# VCO_core.net
KiCad netlist of a schematic drawn in Altium Designer
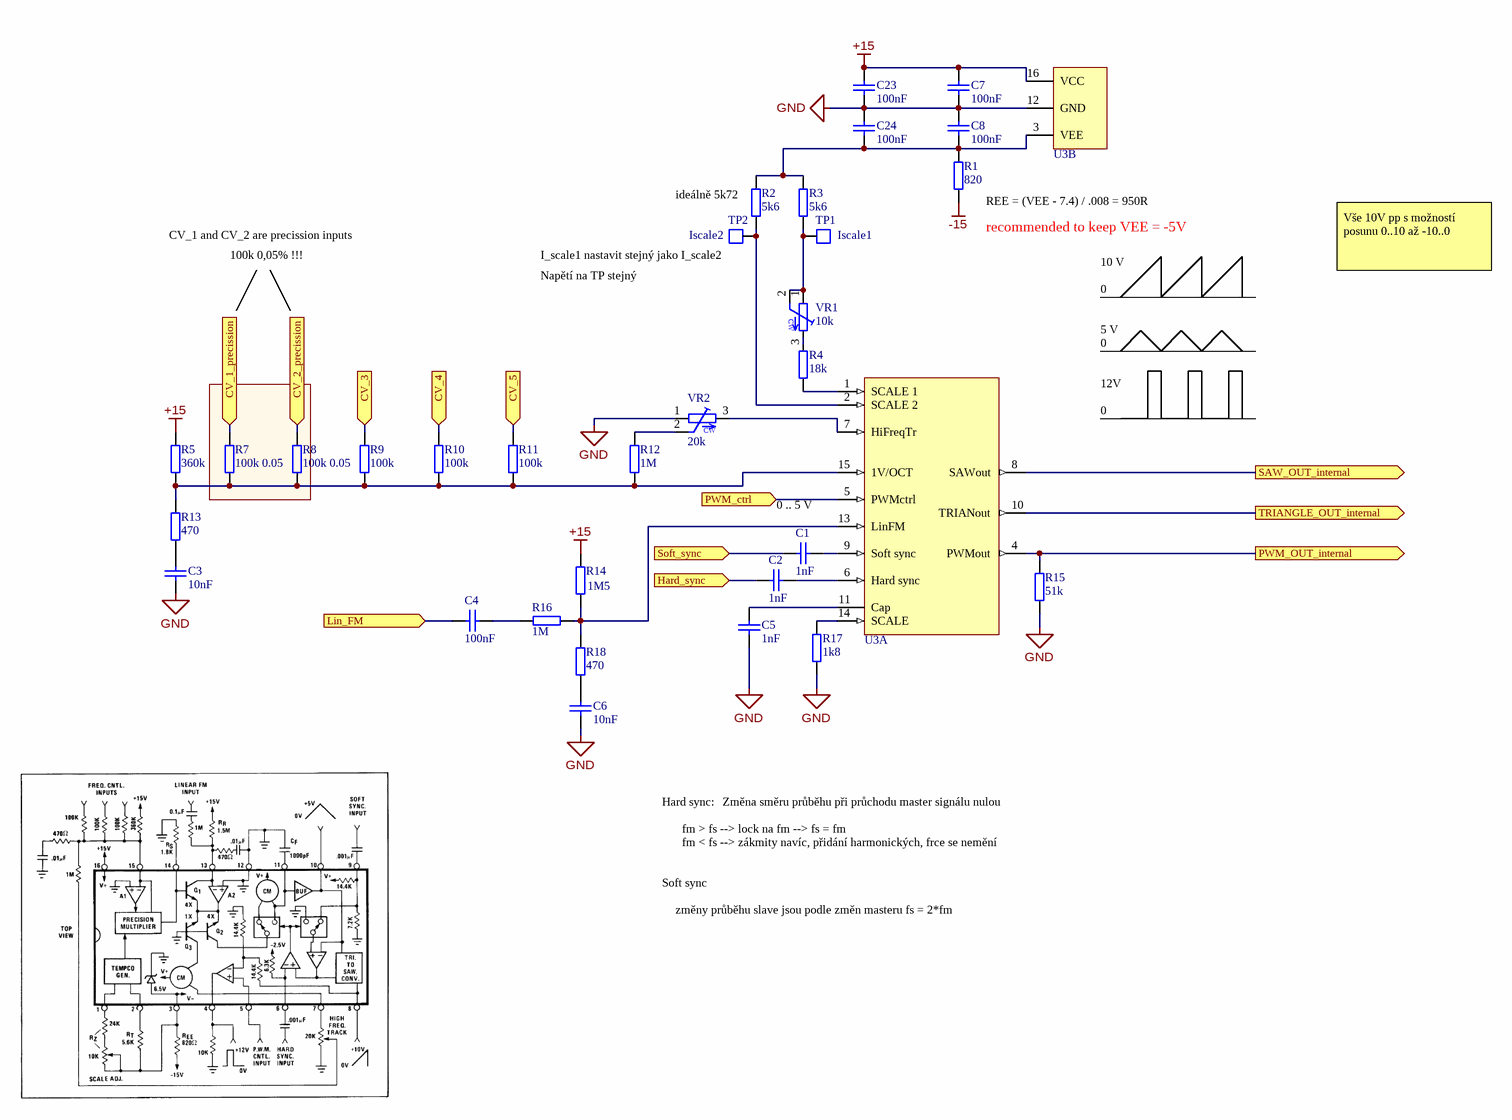
[diagram p0: VCO_core.SchDoc]

(export (version "E")
  (design (tool "Eeschema 10.0.6"))
  (components
    (comp (ref "C1")
      (value "1nF")
      (footprint "WCAP-CSGP_0603_L1.6W0.8H0.8_Reflow")
      (description "WCAP-CSGP Multilayer Ceramic Chip Capacitor, General Purpose, size 0603, NP0, 1nF, 50V")
      (fields
        (field (name "MANUFACTURER") "Wurth Elektronik")
        (field (name "MANUFACTURER PART NUMBER") "885012006063")
      )
      (libsource (lib "Altium_WCAP-CSGP (rev22a)") (part "885012006063"))
    )
    (comp (ref "C2")
      (value "1nF")
      (footprint "WCAP-CSGP_0603_L1.6W0.8H0.8_Reflow")
      (description "WCAP-CSGP Multilayer Ceramic Chip Capacitor, General Purpose, size 0603, NP0, 1nF, 50V")
      (fields
        (field (name "MANUFACTURER") "Wurth Elektronik")
        (field (name "MANUFACTURER PART NUMBER") "885012006063")
      )
      (libsource (lib "Altium_WCAP-CSGP (rev22a)") (part "885012006063"))
    )
    (comp (ref "C3")
      (value "10nF")
      (footprint "WCAP-CSGP_0603_L1.6W0.8H0.8_Reflow")
      (description "WCAP-CSGP Multilayer Ceramic Chip Capacitor, General Purpose, size 0603, X7R, 10nF, 50V")
      (fields
        (field (name "MANUFACTURER") "Wurth Elektronik")
        (field (name "MANUFACTURER PART NUMBER") "885012206089")
      )
      (libsource (lib "Altium_WCAP-CSGP (rev22a)") (part "885012206089"))
    )
    (comp (ref "C4")
      (value "100nF")
      (footprint "WCAP-CSGP_0603_L1.6W0.8H0.8_Reflow")
      (description "WCAP-CSGP Multilayer Ceramic Chip Capacitor, General Purpose, size 0603, X7R, 100nF, 50V")
      (fields
        (field (name "MANUFACTURER") "Wurth Elektronik")
        (field (name "MANUFACTURER PART NUMBER") "885012206095")
      )
      (libsource (lib "Altium_WCAP-CSGP (rev22a)") (part "885012206095"))
    )
    (comp (ref "C5")
      (value "1nF")
      (footprint "WCAP-CSGP_0603_L1.6W0.8H0.8_Reflow")
      (description "WCAP-CSGP Multilayer Ceramic Chip Capacitor, General Purpose, size 0603, NP0, 1nF, 50V")
      (fields
        (field (name "MANUFACTURER") "Wurth Elektronik")
        (field (name "MANUFACTURER PART NUMBER") "885012006063")
      )
      (libsource (lib "Altium_WCAP-CSGP (rev22a)") (part "885012006063"))
    )
    (comp (ref "C6")
      (value "10nF")
      (footprint "WCAP-CSGP_0603_L1.6W0.8H0.8_Reflow")
      (description "WCAP-CSGP Multilayer Ceramic Chip Capacitor, General Purpose, size 0603, X7R, 10nF, 50V")
      (fields
        (field (name "MANUFACTURER") "Wurth Elektronik")
        (field (name "MANUFACTURER PART NUMBER") "885012206089")
      )
      (libsource (lib "Altium_WCAP-CSGP (rev22a)") (part "885012206089"))
    )
    (comp (ref "C7")
      (value "100nF")
      (footprint "WCAP-CSGP_0603_L1.6W0.8H0.8_Reflow")
      (description "WCAP-CSGP Multilayer Ceramic Chip Capacitor, General Purpose, size 0603, X7R, 100nF, 50V")
      (fields
        (field (name "MANUFACTURER") "Wurth Elektronik")
        (field (name "MANUFACTURER PART NUMBER") "885012206095")
      )
      (libsource (lib "Altium_WCAP-CSGP (rev22a)") (part "885012206095"))
    )
    (comp (ref "C8")
      (value "100nF")
      (footprint "WCAP-CSGP_0603_L1.6W0.8H0.8_Reflow")
      (description "WCAP-CSGP Multilayer Ceramic Chip Capacitor, General Purpose, size 0603, X7R, 100nF, 50V")
      (fields
        (field (name "MANUFACTURER") "Wurth Elektronik")
        (field (name "MANUFACTURER PART NUMBER") "885012206095")
      )
      (libsource (lib "Altium_WCAP-CSGP (rev22a)") (part "885012206095"))
    )
    (comp (ref "C23")
      (value "100nF")
      (footprint "WCAP-CSGP_0603_L1.6W0.8H0.8_Reflow")
      (description "WCAP-CSGP Multilayer Ceramic Chip Capacitor, General Purpose, size 0603, X7R, 100nF, 50V")
      (fields
        (field (name "MANUFACTURER") "Wurth Elektronik")
        (field (name "MANUFACTURER PART NUMBER") "885012206095")
      )
      (libsource (lib "Altium_WCAP-CSGP (rev22a)") (part "885012206095"))
    )
    (comp (ref "C24")
      (value "100nF")
      (footprint "WCAP-CSGP_0603_L1.6W0.8H0.8_Reflow")
      (description "WCAP-CSGP Multilayer Ceramic Chip Capacitor, General Purpose, size 0603, X7R, 100nF, 50V")
      (fields
        (field (name "MANUFACTURER") "Wurth Elektronik")
        (field (name "MANUFACTURER PART NUMBER") "885012206095")
      )
      (libsource (lib "Altium_WCAP-CSGP (rev22a)") (part "885012206095"))
    )
    (comp (ref "R1")
      (value "820")
      (footprint "RESC1608X06N(SMR0603)")
      (description "Thick Film resistor, 0603 Size, universal value, 0.1 W")
      (libsource (lib "Kubikova integrovana knihovna ") (part "R 0603 universal"))
    )
    (comp (ref "R2")
      (value "5k6")
      (footprint "RESC1608X06N(SMR0603)")
      (description "Thick Film resistor, 0603 Size, universal value, 0.1 W")
      (libsource (lib "Kubikova integrovana knihovna ") (part "R 0603 universal"))
    )
    (comp (ref "R3")
      (value "5k6")
      (footprint "RESC1608X06N(SMR0603)")
      (description "Thick Film resistor, 0603 Size, universal value, 0.1 W")
      (libsource (lib "Kubikova integrovana knihovna ") (part "R 0603 universal"))
    )
    (comp (ref "R4")
      (value "18k")
      (footprint "RESC1608X06N(SMR0603)")
      (description "Thick Film resistor, 0603 Size, universal value, 0.1 W")
      (libsource (lib "Kubikova integrovana knihovna ") (part "R 0603 universal"))
    )
    (comp (ref "R5")
      (value "360k")
      (footprint "RESC1608X06N(SMR0603)")
      (description "Thick Film resistor, 0603 Size, universal value, 0.1 W")
      (libsource (lib "Kubikova integrovana knihovna ") (part "R 0603 universal"))
    )
    (comp (ref "R7")
      (value "100k 0.05")
      (footprint "RESC1608X06N(SMR0603)")
      (description "Precision Thick Film resistor, 0603 Size, universal value, 0.1 W")
      (libsource (lib "Kubikova integrovana knihovna ") (part "R 0603 universal"))
    )
    (comp (ref "R8")
      (value "100k 0.05")
      (footprint "RESC1608X06N(SMR0603)")
      (description "Precision Thick Film resistor, 0603 Size, universal value, 0.1 W")
      (libsource (lib "Kubikova integrovana knihovna ") (part "R 0603 universal"))
    )
    (comp (ref "R9")
      (value "100k")
      (footprint "RESC1608X06N(SMR0603)")
      (description "Thick Film resistor, 0603 Size, universal value, 0.1 W")
      (libsource (lib "Kubikova integrovana knihovna ") (part "R 0603 universal"))
    )
    (comp (ref "R10")
      (value "100k")
      (footprint "RESC1608X06N(SMR0603)")
      (description "Thick Film resistor, 0603 Size, universal value, 0.1 W")
      (libsource (lib "Kubikova integrovana knihovna ") (part "R 0603 universal"))
    )
    (comp (ref "R11")
      (value "100k")
      (footprint "RESC1608X06N(SMR0603)")
      (description "Thick Film resistor, 0603 Size, universal value, 0.1 W")
      (libsource (lib "Kubikova integrovana knihovna ") (part "R 0603 universal"))
    )
    (comp (ref "R12")
      (value "1M")
      (footprint "RESC1608X06N(SMR0603)")
      (description "Thick Film resistor, 0603 Size, universal value, 0.1 W")
      (libsource (lib "Kubikova integrovana knihovna ") (part "R 0603 universal"))
    )
    (comp (ref "R13")
      (value "470")
      (footprint "RESC1608X06N(SMR0603)")
      (description "Thick Film resistor, 0603 Size, universal value, 0.1 W")
      (libsource (lib "Kubikova integrovana knihovna ") (part "R 0603 universal"))
    )
    (comp (ref "R14")
      (value "1M5")
      (footprint "RESC1608X06N(SMR0603)")
      (description "Thick Film resistor, 0603 Size, universal value, 0.1 W")
      (libsource (lib "Kubikova integrovana knihovna ") (part "R 0603 universal"))
    )
    (comp (ref "R15")
      (value "51k")
      (footprint "RESC1608X06N(SMR0603)")
      (description "Thick Film resistor, 0603 Size, universal value, 0.1 W")
      (libsource (lib "Kubikova integrovana knihovna ") (part "R 0603 universal"))
    )
    (comp (ref "R16")
      (value "1M")
      (footprint "RESC1608X06N(SMR0603)")
      (description "Thick Film resistor, 0603 Size, universal value, 0.1 W")
      (libsource (lib "Kubikova integrovana knihovna ") (part "R 0603 universal"))
    )
    (comp (ref "R17")
      (value "1k8")
      (footprint "RESC1608X06N(SMR0603)")
      (description "Thick Film resistor, 0603 Size, universal value, 0.1 W")
      (libsource (lib "Kubikova integrovana knihovna ") (part "R 0603 universal"))
    )
    (comp (ref "R18")
      (value "470")
      (footprint "RESC1608X06N(SMR0603)")
      (description "Thick Film resistor, 0603 Size, universal value, 0.1 W")
      (libsource (lib "Kubikova integrovana knihovna ") (part "R 0603 universal"))
    )
    (comp (ref "TP1")
      (value "Iscale1")
      (footprint "TP_1.5_SMD_ROUND")
      (description "De; Test Point;")
      (libsource (lib "altium_sql") (part "TEST_POINT_SMD_ROUND"))
    )
    (comp (ref "TP2")
      (value "Iscale2")
      (footprint "TP_1.5_SMD_ROUND")
      (description "De; Test Point;")
      (libsource (lib "altium_sql") (part "TEST_POINT_SMD_ROUND"))
    )
    (comp (ref "U3")
      (value "CEM3340")
      (footprint "DIP-16")
      (description "ALFA RPAR AS3340 VCO (CEM3340)")
      (libsource (lib "") (part "CEM3340_1"))
    )
    (comp (ref "VR1")
      (value "10k")
      (footprint "64W")
      (description "093 - 3/8\" Square (10 mm) Multi-Turn Cermet Trimmer")
      (libsource (lib "Kubikova integrovana knihovna ") (part "Trimmer universal 3/8 (10mm)"))
    )
    (comp (ref "VR2")
      (value "20k")
      (footprint "64W")
      (description "093 - 3/8\" Square (10 mm) Multi-Turn Cermet Trimmer")
      (libsource (lib "Kubikova integrovana knihovna ") (part "Trimmer universal 3/8 (10mm)"))
    )
  )
  (nets
    (net (code "1") (name "+15") (class "Default")
      (node (ref "C23") (pin "2") (pinfunction "2_2") (pintype "passive"))
      (node (ref "C7") (pin "2") (pinfunction "2_2") (pintype "passive"))
      (node (ref "R14") (pin "2") (pinfunction "2_2") (pintype "passive"))
      (node (ref "R5") (pin "1") (pinfunction "1_1") (pintype "passive"))
      (node (ref "U3") (pin "16") (pinfunction "VCC_16") (pintype "power_in"))
    )
    (net (code "2") (name "-15") (class "Default")
      (node (ref "R1") (pin "1") (pinfunction "1_1") (pintype "passive"))
    )
    (net (code "3") (name "/CV_1_precission") (class "Default")
      (node (ref "R7") (pin "1") (pinfunction "1_1") (pintype "passive"))
    )
    (net (code "4") (name "/CV_2_precission") (class "Default")
      (node (ref "R8") (pin "1") (pinfunction "1_1") (pintype "passive"))
    )
    (net (code "5") (name "/CV_3") (class "Default")
      (node (ref "R9") (pin "1") (pinfunction "1_1") (pintype "passive"))
    )
    (net (code "6") (name "/CV_4") (class "Default")
      (node (ref "R10") (pin "1") (pinfunction "1_1") (pintype "passive"))
    )
    (net (code "7") (name "/CV_5") (class "Default")
      (node (ref "R11") (pin "1") (pinfunction "1_1") (pintype "passive"))
    )
    (net (code "8") (name "/Hard_sync") (class "Default")
      (node (ref "C2") (pin "1") (pinfunction "1_1") (pintype "passive"))
    )
    (net (code "9") (name "/Lin_FM") (class "Default")
      (node (ref "C4") (pin "1") (pinfunction "1_1") (pintype "passive"))
    )
    (net (code "10") (name "/PWM_OUT_internal") (class "Default")
      (node (ref "R15") (pin "2") (pinfunction "2_2") (pintype "passive"))
      (node (ref "U3") (pin "4") (pinfunction "PWMout_4") (pintype "output"))
    )
    (net (code "11") (name "/PWM_ctrl") (class "Default")
      (node (ref "U3") (pin "5") (pinfunction "PWMctrl_5") (pintype "input"))
    )
    (net (code "12") (name "/SAW_OUT_internal") (class "Default")
      (node (ref "U3") (pin "8") (pinfunction "SAWout_8") (pintype "output"))
    )
    (net (code "13") (name "/Soft_sync") (class "Default")
      (node (ref "C1") (pin "1") (pinfunction "1_1") (pintype "passive"))
    )
    (net (code "14") (name "/TRIANGLE_OUT_internal") (class "Default")
      (node (ref "U3") (pin "10") (pinfunction "TRIANout_10") (pintype "output"))
    )
    (net (code "15") (name "GND") (class "Default")
      (node (ref "C23") (pin "1") (pinfunction "1_1") (pintype "passive"))
      (node (ref "C24") (pin "2") (pinfunction "2_2") (pintype "passive"))
      (node (ref "C3") (pin "2") (pinfunction "2_2") (pintype "passive"))
      (node (ref "C5") (pin "1") (pinfunction "1_1") (pintype "passive"))
      (node (ref "C6") (pin "1") (pinfunction "1_1") (pintype "passive"))
      (node (ref "C7") (pin "1") (pinfunction "1_1") (pintype "passive"))
      (node (ref "C8") (pin "2") (pinfunction "2_2") (pintype "passive"))
      (node (ref "R15") (pin "1") (pinfunction "1_1") (pintype "passive"))
      (node (ref "R17") (pin "1") (pinfunction "1_1") (pintype "passive"))
      (node (ref "U3") (pin "12") (pinfunction "GND_12") (pintype "power_in"))
      (node (ref "VR2") (pin "1") (pinfunction "1_1") (pintype "passive"))
    )
    (net (code "16") (name "Net-(C3-Pad1)") (class "Default")
      (node (ref "C3") (pin "1") (pinfunction "1_1") (pintype "passive"))
      (node (ref "R13") (pin "2") (pinfunction "2_2") (pintype "passive"))
    )
    (net (code "17") (name "Net-(C4-Pad2)") (class "Default")
      (node (ref "C4") (pin "2") (pinfunction "2_2") (pintype "passive"))
      (node (ref "R16") (pin "2") (pinfunction "2_2") (pintype "passive"))
    )
    (net (code "18") (name "Net-(C6-Pad2)") (class "Default")
      (node (ref "C6") (pin "2") (pinfunction "2_2") (pintype "passive"))
      (node (ref "R18") (pin "1") (pinfunction "1_1") (pintype "passive"))
    )
    (net (code "19") (name "Net-(R3-Pad1)") (class "Default")
      (node (ref "R3") (pin "1") (pinfunction "1_1") (pintype "passive"))
      (node (ref "TP1") (pin "1") (pintype "passive"))
      (node (ref "VR1") (pin "1") (pinfunction "1_1") (pintype "passive"))
      (node (ref "VR1") (pin "2") (pinfunction "2_2") (pintype "passive"))
    )
    (net (code "20") (name "Net-(R4-Pad1)") (class "Default")
      (node (ref "R4") (pin "1") (pinfunction "1_1") (pintype "passive"))
      (node (ref "VR1") (pin "3") (pinfunction "3_3") (pintype "passive"))
    )
    (net (code "21") (name "Net-(R12-Pad2)") (class "Default")
      (node (ref "R12") (pin "2") (pinfunction "2_2") (pintype "passive"))
      (node (ref "VR2") (pin "2") (pinfunction "2_2") (pintype "passive"))
    )
    (net (code "22") (name "Net-(U3A-1V{slash}OCT)") (class "Default")
      (node (ref "R10") (pin "2") (pinfunction "2_2") (pintype "passive"))
      (node (ref "R11") (pin "2") (pinfunction "2_2") (pintype "passive"))
      (node (ref "R12") (pin "1") (pinfunction "1_1") (pintype "passive"))
      (node (ref "R13") (pin "1") (pinfunction "1_1") (pintype "passive"))
      (node (ref "R5") (pin "2") (pinfunction "2_2") (pintype "passive"))
      (node (ref "R7") (pin "2") (pinfunction "2_2") (pintype "passive"))
      (node (ref "R8") (pin "2") (pinfunction "2_2") (pintype "passive"))
      (node (ref "R9") (pin "2") (pinfunction "2_2") (pintype "passive"))
      (node (ref "U3") (pin "15") (pinfunction "1V/OCT_15") (pintype "input"))
    )
    (net (code "23") (name "Net-(U3A-Cap)") (class "Default")
      (node (ref "C5") (pin "2") (pinfunction "2_2") (pintype "passive"))
      (node (ref "U3") (pin "11") (pinfunction "Cap_11") (pintype "power_in"))
    )
    (net (code "24") (name "Net-(U3A-Hard_sync)") (class "Default")
      (node (ref "C2") (pin "2") (pinfunction "2_2") (pintype "passive"))
      (node (ref "U3") (pin "6") (pinfunction "Hard_sync_6") (pintype "input"))
    )
    (net (code "25") (name "Net-(U3A-HiFreqTr)") (class "Default")
      (node (ref "U3") (pin "7") (pinfunction "HiFreqTr_7") (pintype "input"))
      (node (ref "VR2") (pin "3") (pinfunction "3_3") (pintype "passive"))
    )
    (net (code "26") (name "Net-(U3A-LinFM)") (class "Default")
      (node (ref "R14") (pin "1") (pinfunction "1_1") (pintype "passive"))
      (node (ref "R16") (pin "1") (pinfunction "1_1") (pintype "passive"))
      (node (ref "R18") (pin "2") (pinfunction "2_2") (pintype "passive"))
      (node (ref "U3") (pin "13") (pinfunction "LinFM_13") (pintype "input"))
    )
    (net (code "27") (name "Net-(U3A-SCALE)") (class "Default")
      (node (ref "R17") (pin "2") (pinfunction "2_2") (pintype "passive"))
      (node (ref "U3") (pin "14") (pinfunction "SCALE_14") (pintype "input"))
    )
    (net (code "28") (name "Net-(U3A-SCALE_1)") (class "Default")
      (node (ref "R4") (pin "2") (pinfunction "2_2") (pintype "passive"))
      (node (ref "U3") (pin "1") (pinfunction "SCALE_1_1") (pintype "input"))
    )
    (net (code "29") (name "Net-(U3A-SCALE_2)") (class "Default")
      (node (ref "R2") (pin "1") (pinfunction "1_1") (pintype "passive"))
      (node (ref "TP2") (pin "1") (pintype "passive"))
      (node (ref "U3") (pin "2") (pinfunction "SCALE_2_2") (pintype "input"))
    )
    (net (code "30") (name "Net-(U3A-Soft_sync)") (class "Default")
      (node (ref "C1") (pin "2") (pinfunction "2_2") (pintype "passive"))
      (node (ref "U3") (pin "9") (pinfunction "Soft_sync_9") (pintype "input"))
    )
    (net (code "31") (name "Net-(U3B-VEE)") (class "Default")
      (node (ref "C24") (pin "1") (pinfunction "1_1") (pintype "passive"))
      (node (ref "C8") (pin "1") (pinfunction "1_1") (pintype "passive"))
      (node (ref "R1") (pin "2") (pinfunction "2_2") (pintype "passive"))
      (node (ref "R2") (pin "2") (pinfunction "2_2") (pintype "passive"))
      (node (ref "R3") (pin "2") (pinfunction "2_2") (pintype "passive"))
      (node (ref "U3") (pin "3") (pinfunction "VEE_3") (pintype "power_in"))
    )
  )
)
